# MAPE-CUN-Large-010.net
KiCad netlist of a schematic drawn in EAGLE
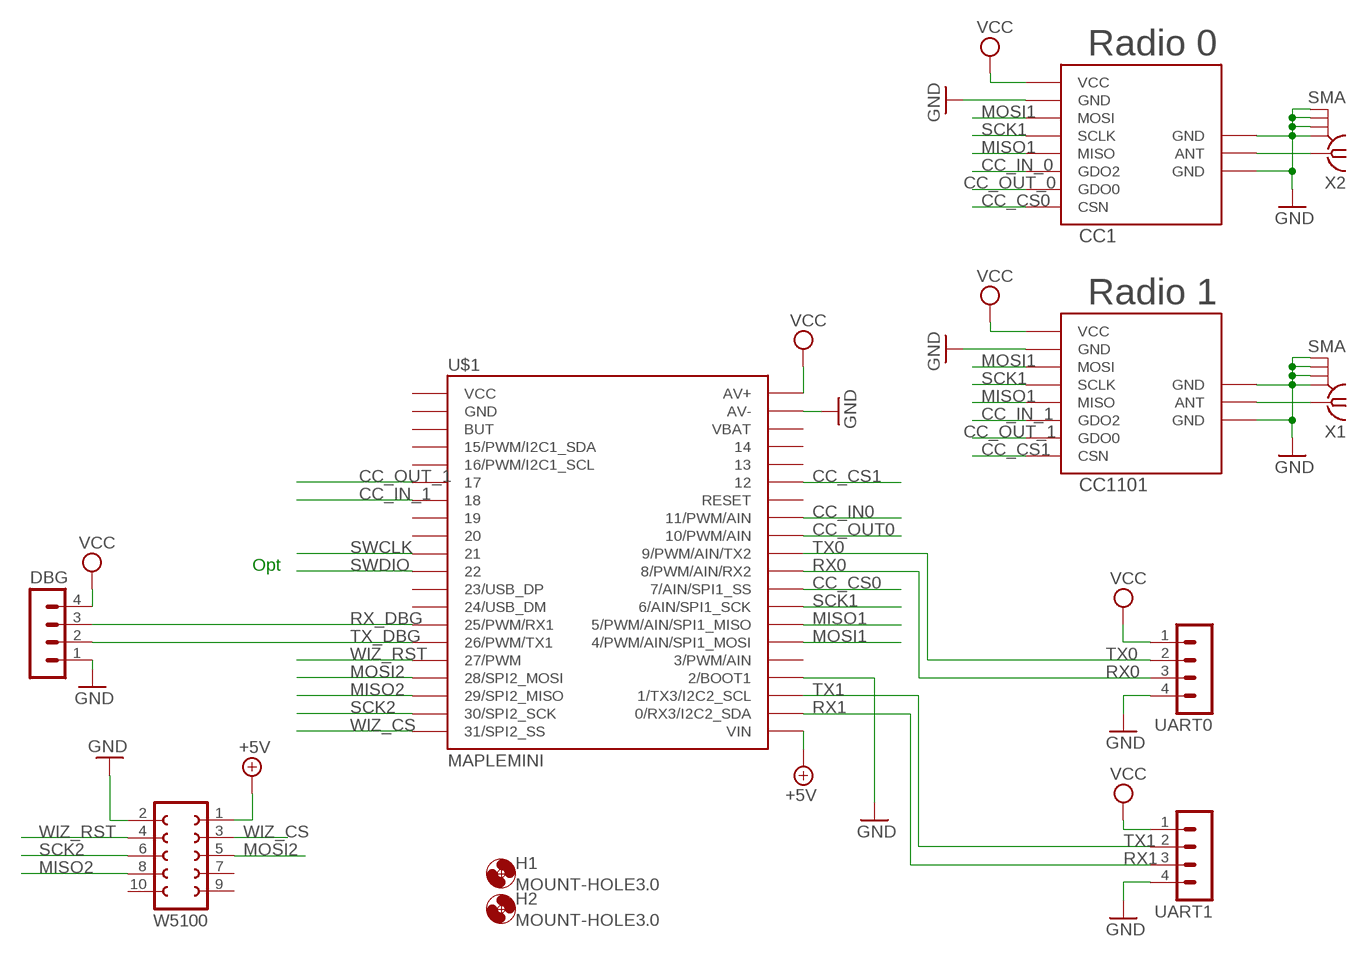
[diagram p0: schematic, sheet 1]

(export (version "E")
  (design (tool "Eeschema 10.0.6"))
  (components
    (comp (ref "CC1")
      (value "CC1101_MODULE1SMD")
      (footprint "eagle-import:CC1101_MODULE1_SMD")
      (libsource (lib "eagle-import") (part "CC1101_MODULE1SMD"))
    )
    (comp (ref "CC1101")
      (value "CC1101_MODULE1SMD")
      (footprint "eagle-import:CC1101_MODULE1_SMD")
      (libsource (lib "eagle-import") (part "CC1101_MODULE1SMD"))
    )
    (comp (ref "DBG")
      (value "MA04-1")
      (footprint "eagle-import:MA04-1")
      (libsource (lib "eagle-import") (part "MA04-1"))
    )
    (comp (ref "H1")
      (value "MOUNT-HOLE3.0")
      (footprint "eagle-import:3,0")
      (libsource (lib "eagle-import") (part "MOUNT-HOLE3.0"))
    )
    (comp (ref "H2")
      (value "MOUNT-HOLE3.0")
      (footprint "eagle-import:3,0")
      (libsource (lib "eagle-import") (part "MOUNT-HOLE3.0"))
    )
    (comp (ref "U$1")
      (value "MAPLEMINI")
      (footprint "eagle-import:20-DIP")
      (libsource (lib "eagle-import") (part "MAPLEMINI"))
    )
    (comp (ref "UART0")
      (value "MA04-1")
      (footprint "eagle-import:MA04-1")
      (libsource (lib "eagle-import") (part "MA04-1"))
    )
    (comp (ref "UART1")
      (value "MA04-1")
      (footprint "eagle-import:MA04-1")
      (libsource (lib "eagle-import") (part "MA04-1"))
    )
    (comp (ref "W5100")
      (value "FE05-2")
      (footprint "eagle-import:FE05-2")
      (libsource (lib "eagle-import") (part "FE05-2"))
    )
    (comp (ref "X1")
      (value "SMA")
      (footprint "eagle-import:SMA")
      (libsource (lib "eagle-import") (part "SMA"))
    )
    (comp (ref "X2")
      (value "SMA")
      (footprint "eagle-import:SMA")
      (libsource (lib "eagle-import") (part "SMA"))
    )
  )
  (nets
    (net (code "1") (name "+5V") (class "Default")
      (node (ref "U$1") (pin "21") (pinfunction "VIN_21") (pintype "bidirectional"))
      (node (ref "W5100") (pin "1") (pinfunction "1_1") (pintype "passive"))
    )
    (net (code "2") (name "/CC_CS0") (class "Default")
      (node (ref "CC1") (pin "CSN") (pinfunction "CSN_CSN") (pintype "bidirectional"))
      (node (ref "U$1") (pin "29") (pinfunction "7/AIN/SPI1_SS_29") (pintype "bidirectional"))
    )
    (net (code "3") (name "/CC_CS1") (class "Default")
      (node (ref "CC1101") (pin "CSN") (pinfunction "CSN_CSN") (pintype "bidirectional"))
      (node (ref "U$1") (pin "35") (pinfunction "12_35") (pintype "bidirectional"))
    )
    (net (code "4") (name "/CC_IN0") (class "Default")
      (node (ref "U$1") (pin "33") (pinfunction "11/PWM/AIN_33") (pintype "bidirectional"))
    )
    (net (code "5") (name "/CC_IN_0") (class "Default")
      (node (ref "CC1") (pin "GDO2") (pinfunction "GDO2_GDO2") (pintype "bidirectional"))
    )
    (net (code "6") (name "/CC_IN_1") (class "Default")
      (node (ref "CC1101") (pin "GDO2") (pinfunction "GDO2_GDO2") (pintype "bidirectional"))
      (node (ref "U$1") (pin "7") (pinfunction "18_7") (pintype "bidirectional"))
    )
    (net (code "7") (name "/CC_OUT0") (class "Default")
      (node (ref "U$1") (pin "32") (pinfunction "10/PWM/AIN_32") (pintype "bidirectional"))
    )
    (net (code "8") (name "/CC_OUT_0") (class "Default")
      (node (ref "CC1") (pin "GDO0") (pinfunction "GDO0_GDO0") (pintype "bidirectional"))
    )
    (net (code "9") (name "/CC_OUT_1") (class "Default")
      (node (ref "CC1101") (pin "GDO0") (pinfunction "GDO0_GDO0") (pintype "bidirectional"))
      (node (ref "U$1") (pin "6") (pinfunction "17_6") (pintype "bidirectional"))
    )
    (net (code "10") (name "/MISO1") (class "Default")
      (node (ref "CC1") (pin "MISO") (pinfunction "MISO_MISO") (pintype "bidirectional"))
      (node (ref "CC1101") (pin "MISO") (pinfunction "MISO_MISO") (pintype "bidirectional"))
      (node (ref "U$1") (pin "27") (pinfunction "5/PWM/AIN/SPI1_MISO_27") (pintype "bidirectional"))
    )
    (net (code "11") (name "/MISO2") (class "Default")
      (node (ref "U$1") (pin "18") (pinfunction "29/SPI2_MISO_18") (pintype "bidirectional"))
      (node (ref "W5100") (pin "8") (pinfunction "8_8") (pintype "passive"))
    )
    (net (code "12") (name "/MOSI1") (class "Default")
      (node (ref "CC1") (pin "MOSI") (pinfunction "MOSI_MOSI") (pintype "bidirectional"))
      (node (ref "CC1101") (pin "MOSI") (pinfunction "MOSI_MOSI") (pintype "bidirectional"))
      (node (ref "U$1") (pin "26") (pinfunction "4/PWM/AIN/SPI1_MOSI_26") (pintype "bidirectional"))
    )
    (net (code "13") (name "/MOSI2") (class "Default")
      (node (ref "U$1") (pin "17") (pinfunction "28/SPI2_MOSI_17") (pintype "bidirectional"))
      (node (ref "W5100") (pin "5") (pinfunction "5_5") (pintype "passive"))
    )
    (net (code "14") (name "/RX0") (class "Default")
      (node (ref "U$1") (pin "30") (pinfunction "8/PWM/AIN/RX2_30") (pintype "bidirectional"))
      (node (ref "UART0") (pin "3") (pinfunction "3_3") (pintype "passive"))
    )
    (net (code "15") (name "/RX1") (class "Default")
      (node (ref "U$1") (pin "22") (pinfunction "0/RX3/I2C2_SDA_22") (pintype "bidirectional"))
      (node (ref "UART1") (pin "3") (pinfunction "3_3") (pintype "passive"))
    )
    (net (code "16") (name "/RX_DBG") (class "Default")
      (node (ref "DBG") (pin "3") (pinfunction "3_3") (pintype "passive"))
      (node (ref "U$1") (pin "14") (pinfunction "25/PWM/RX1_14") (pintype "bidirectional"))
    )
    (net (code "17") (name "/SCK1") (class "Default")
      (node (ref "CC1") (pin "SCLK") (pinfunction "SCLK_SCLK") (pintype "bidirectional"))
      (node (ref "CC1101") (pin "SCLK") (pinfunction "SCLK_SCLK") (pintype "bidirectional"))
      (node (ref "U$1") (pin "28") (pinfunction "6/AIN/SPI1_SCK_28") (pintype "bidirectional"))
    )
    (net (code "18") (name "/SCK2") (class "Default")
      (node (ref "U$1") (pin "19") (pinfunction "30/SPI2_SCK_19") (pintype "bidirectional"))
      (node (ref "W5100") (pin "6") (pinfunction "6_6") (pintype "passive"))
    )
    (net (code "19") (name "/SWCLK") (class "Default")
      (node (ref "U$1") (pin "10") (pinfunction "21_10") (pintype "bidirectional"))
    )
    (net (code "20") (name "/SWDIO") (class "Default")
      (node (ref "U$1") (pin "11") (pinfunction "22_11") (pintype "bidirectional"))
    )
    (net (code "21") (name "/TX0") (class "Default")
      (node (ref "U$1") (pin "31") (pinfunction "9/PWM/AIN/TX2_31") (pintype "bidirectional"))
      (node (ref "UART0") (pin "2") (pinfunction "2_2") (pintype "passive"))
    )
    (net (code "22") (name "/TX1") (class "Default")
      (node (ref "U$1") (pin "23") (pinfunction "1/TX3/I2C2_SCL_23") (pintype "bidirectional"))
      (node (ref "UART1") (pin "2") (pinfunction "2_2") (pintype "passive"))
    )
    (net (code "23") (name "/TX_DBG") (class "Default")
      (node (ref "DBG") (pin "2") (pinfunction "2_2") (pintype "passive"))
      (node (ref "U$1") (pin "15") (pinfunction "26/PWM/TX1_15") (pintype "bidirectional"))
    )
    (net (code "24") (name "/WIZ_CS") (class "Default")
      (node (ref "U$1") (pin "20") (pinfunction "31/SPI2_SS_20") (pintype "bidirectional"))
      (node (ref "W5100") (pin "3") (pinfunction "3_3") (pintype "passive"))
    )
    (net (code "25") (name "/WIZ_RST") (class "Default")
      (node (ref "U$1") (pin "16") (pinfunction "27/PWM_16") (pintype "bidirectional"))
      (node (ref "W5100") (pin "4") (pinfunction "4_4") (pintype "passive"))
    )
    (net (code "26") (name "GND") (class "Default")
      (node (ref "CC1") (pin "GND@0") (pinfunction "GND_GND@0") (pintype "power_in"))
      (node (ref "CC1") (pin "GND@1") (pinfunction "GND_GND@1") (pintype "power_in"))
      (node (ref "CC1") (pin "GND@2") (pinfunction "GND_GND@2") (pintype "power_in"))
      (node (ref "CC1101") (pin "GND@0") (pinfunction "GND_GND@0") (pintype "power_in"))
      (node (ref "CC1101") (pin "GND@1") (pinfunction "GND_GND@1") (pintype "power_in"))
      (node (ref "CC1101") (pin "GND@2") (pinfunction "GND_GND@2") (pintype "power_in"))
      (node (ref "DBG") (pin "1") (pinfunction "1_1") (pintype "passive"))
      (node (ref "U$1") (pin "24") (pinfunction "2/BOOT1_24") (pintype "bidirectional"))
      (node (ref "U$1") (pin "39") (pinfunction "AV-_39") (pintype "bidirectional"))
      (node (ref "UART0") (pin "4") (pinfunction "4_4") (pintype "passive"))
      (node (ref "UART1") (pin "4") (pinfunction "4_4") (pintype "passive"))
      (node (ref "W5100") (pin "2") (pinfunction "2_2") (pintype "passive"))
      (node (ref "X1") (pin "GND@1") (pinfunction "2_GND@1") (pintype "passive"))
      (node (ref "X1") (pin "GND@2") (pinfunction "3_GND@2") (pintype "passive"))
      (node (ref "X1") (pin "GND@3") (pinfunction "4_GND@3") (pintype "passive"))
      (node (ref "X1") (pin "GND@4") (pinfunction "5_GND@4") (pintype "passive"))
      (node (ref "X2") (pin "GND@1") (pinfunction "2_GND@1") (pintype "passive"))
      (node (ref "X2") (pin "GND@2") (pinfunction "3_GND@2") (pintype "passive"))
      (node (ref "X2") (pin "GND@3") (pinfunction "4_GND@3") (pintype "passive"))
      (node (ref "X2") (pin "GND@4") (pinfunction "5_GND@4") (pintype "passive"))
    )
    (net (code "27") (name "Net-(CC1-PadANT)") (class "Default")
      (node (ref "CC1") (pin "ANT") (pinfunction "ANT_ANT") (pintype "output"))
      (node (ref "X2") (pin "1") (pinfunction "1_1") (pintype "passive"))
    )
    (net (code "28") (name "Net-(CC1101-PadANT)") (class "Default")
      (node (ref "CC1101") (pin "ANT") (pinfunction "ANT_ANT") (pintype "output"))
      (node (ref "X1") (pin "1") (pinfunction "1_1") (pintype "passive"))
    )
    (net (code "29") (name "VCC") (class "Default")
      (node (ref "CC1") (pin "VCC") (pinfunction "VCC_VCC") (pintype "power_in"))
      (node (ref "CC1101") (pin "VCC") (pinfunction "VCC_VCC") (pintype "power_in"))
      (node (ref "DBG") (pin "4") (pinfunction "4_4") (pintype "passive"))
      (node (ref "U$1") (pin "40") (pinfunction "AV+_40") (pintype "bidirectional"))
      (node (ref "UART0") (pin "1") (pinfunction "1_1") (pintype "passive"))
      (node (ref "UART1") (pin "1") (pinfunction "1_1") (pintype "passive"))
    )
    (net (code "30") (name "unconnected-(U$1-3{slash}PWM{slash}AIN-Pad25)") (class "Default")
      (node (ref "U$1") (pin "25") (pinfunction "3/PWM/AIN_25") (pintype "bidirectional"))
    )
    (net (code "31") (name "unconnected-(U$1-13-Pad36)") (class "Default")
      (node (ref "U$1") (pin "36") (pinfunction "13_36") (pintype "bidirectional"))
    )
    (net (code "32") (name "unconnected-(U$1-14-Pad37)") (class "Default")
      (node (ref "U$1") (pin "37") (pinfunction "14_37") (pintype "bidirectional"))
    )
    (net (code "33") (name "unconnected-(U$1-15{slash}PWM{slash}I2C1_SDA-Pad4)") (class "Default")
      (node (ref "U$1") (pin "4") (pinfunction "15/PWM/I2C1_SDA_4") (pintype "bidirectional"))
    )
    (net (code "34") (name "unconnected-(U$1-16{slash}PWM{slash}I2C1_SCL-Pad5)") (class "Default")
      (node (ref "U$1") (pin "5") (pinfunction "16/PWM/I2C1_SCL_5") (pintype "bidirectional"))
    )
    (net (code "35") (name "unconnected-(U$1-19-Pad8)") (class "Default")
      (node (ref "U$1") (pin "8") (pinfunction "19_8") (pintype "bidirectional"))
    )
    (net (code "36") (name "unconnected-(U$1-20-Pad9)") (class "Default")
      (node (ref "U$1") (pin "9") (pinfunction "20_9") (pintype "bidirectional"))
    )
    (net (code "37") (name "unconnected-(U$1-23{slash}USB_DP-Pad12)") (class "Default")
      (node (ref "U$1") (pin "12") (pinfunction "23/USB_DP_12") (pintype "bidirectional"))
    )
    (net (code "38") (name "unconnected-(U$1-24{slash}USB_DM-Pad13)") (class "Default")
      (node (ref "U$1") (pin "13") (pinfunction "24/USB_DM_13") (pintype "bidirectional"))
    )
    (net (code "39") (name "unconnected-(U$1-BUT-Pad3)") (class "Default")
      (node (ref "U$1") (pin "3") (pinfunction "BUT_3") (pintype "bidirectional"))
    )
    (net (code "40") (name "unconnected-(U$1-GND-Pad2)") (class "Default")
      (node (ref "U$1") (pin "2") (pinfunction "GND_2") (pintype "bidirectional"))
    )
    (net (code "41") (name "unconnected-(U$1-RESET-Pad34)") (class "Default")
      (node (ref "U$1") (pin "34") (pinfunction "RESET_34") (pintype "bidirectional"))
    )
    (net (code "42") (name "unconnected-(U$1-VBAT-Pad38)") (class "Default")
      (node (ref "U$1") (pin "38") (pinfunction "VBAT_38") (pintype "bidirectional"))
    )
    (net (code "43") (name "unconnected-(U$1-VCC-Pad1)") (class "Default")
      (node (ref "U$1") (pin "1") (pinfunction "VCC_1") (pintype "bidirectional"))
    )
    (net (code "44") (name "unconnected-(W5100-Pad7)") (class "Default")
      (node (ref "W5100") (pin "7") (pinfunction "7_7") (pintype "passive"))
    )
    (net (code "45") (name "unconnected-(W5100-Pad9)") (class "Default")
      (node (ref "W5100") (pin "9") (pinfunction "9_9") (pintype "passive"))
    )
    (net (code "46") (name "unconnected-(W5100-Pad10)") (class "Default")
      (node (ref "W5100") (pin "10") (pinfunction "10_10") (pintype "passive"))
    )
  )
)
